# 5V_LS.net
KiCad netlist of a schematic drawn in Altium Designer
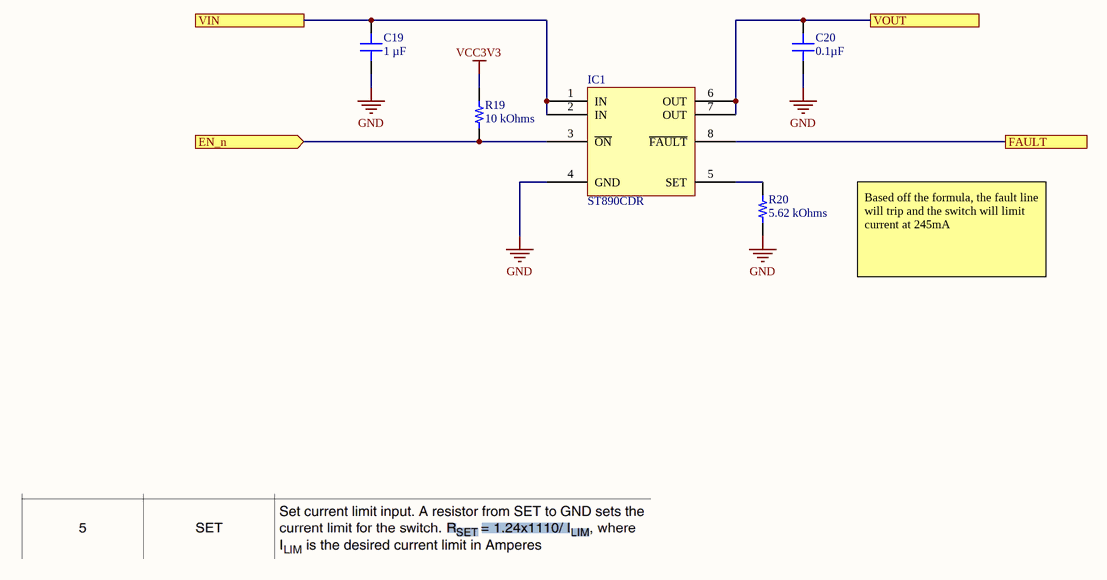
[diagram p0: 5V_LS.SchDoc]

(export (version "E")
  (design (tool "Eeschema 10.0.6"))
  (components
    (comp (ref "C19")
      (value "1 µF")
      (footprint "CAP 0402_1005")
      (description "CAP CER 1UF 10V X7S 0402")
      (fields
        (field (name "PART NUMBER") "GRM155C71A105KE11D")
        (field (name "MANUFACTURER") "Murata Electronics")
      )
      (libsource (lib "Celestial") (part "Capacitor"))
    )
    (comp (ref "C20")
      (value "0.1µF")
      (footprint "CAP 0402_1005")
      (description "CAP CER 0.1UF 10V X7R 0402")
      (fields (field (name "PART NUMBER") "0402ZC104KAT2A") (field (name "MANUFACTURER") "AVX Corporation"))
      (libsource (lib "Celestial") (part "Capacitor"))
    )
    (comp (ref "IC1")
      (value "ST890CDR")
      (footprint "ST SOIC-8N")
      (description "IC PWR SWITCH P-CHANNEL 1:1 8SO")
      (fields (field (name "MANUFACTURER") "STMicroelectronics"))
      (libsource (lib "Celestial") (part "ST ST890CDR"))
    )
    (comp (ref "R19")
      (value "10 kOhms")
      (footprint "RES 0402_1005")
      (description "RES 10K OHM 0.1% 1/10W 0402")
      (fields
        (field (name "PART NUMBER") "RP73PF1E10KBTD")
        (field (name "MANUFACTURER") "TE Connectivity Passive Product")
      )
      (libsource (lib "Celestial") (part "Resistor"))
    )
    (comp (ref "R20")
      (value "5.62 kOhms")
      (footprint "RES 0402_1005")
      (description "RES 5.62K OHM 0.1% 1/10W 0402")
      (fields
        (field (name "PART NUMBER") "RP73PF1E5K62BTD")
        (field (name "MANUFACTURER") "TE Connectivity Passive Product")
      )
      (libsource (lib "Celestial") (part "Resistor"))
    )
  )
  (nets
    (net (code "1") (name "/EN_n") (class "Default")
      (node (ref "IC1") (pin "3") (pinfunction "~{ON}_3") (pintype "passive"))
      (node (ref "R19") (pin "1") (pinfunction "1_1") (pintype "passive"))
    )
    (net (code "2") (name "/FAULT") (class "Default")
      (node (ref "IC1") (pin "8") (pinfunction "~{FAULT}_8") (pintype "passive"))
    )
    (net (code "3") (name "/VIN") (class "Default")
      (node (ref "C19") (pin "2") (pinfunction "2_2") (pintype "passive"))
      (node (ref "IC1") (pin "1") (pinfunction "IN_1") (pintype "passive"))
      (node (ref "IC1") (pin "2") (pinfunction "IN_2") (pintype "passive"))
    )
    (net (code "4") (name "/VOUT") (class "Default")
      (node (ref "C20") (pin "2") (pinfunction "2_2") (pintype "passive"))
      (node (ref "IC1") (pin "6") (pinfunction "OUT_6") (pintype "passive"))
      (node (ref "IC1") (pin "7") (pinfunction "OUT_7") (pintype "passive"))
    )
    (net (code "5") (name "GND") (class "Default")
      (node (ref "C19") (pin "1") (pinfunction "1_1") (pintype "passive"))
      (node (ref "C20") (pin "1") (pinfunction "1_1") (pintype "passive"))
      (node (ref "IC1") (pin "4") (pinfunction "GND_4") (pintype "passive"))
      (node (ref "R20") (pin "1") (pinfunction "1_1") (pintype "passive"))
    )
    (net (code "6") (name "Net-(IC1-SET)") (class "Default")
      (node (ref "IC1") (pin "5") (pinfunction "SET_5") (pintype "passive"))
      (node (ref "R20") (pin "2") (pinfunction "2_2") (pintype "passive"))
    )
    (net (code "7") (name "VCC3V3") (class "Default")
      (node (ref "R19") (pin "2") (pinfunction "2_2") (pintype "passive"))
    )
  )
)
